# motor_sch.net
KiCad netlist of a schematic drawn in Altium Designer
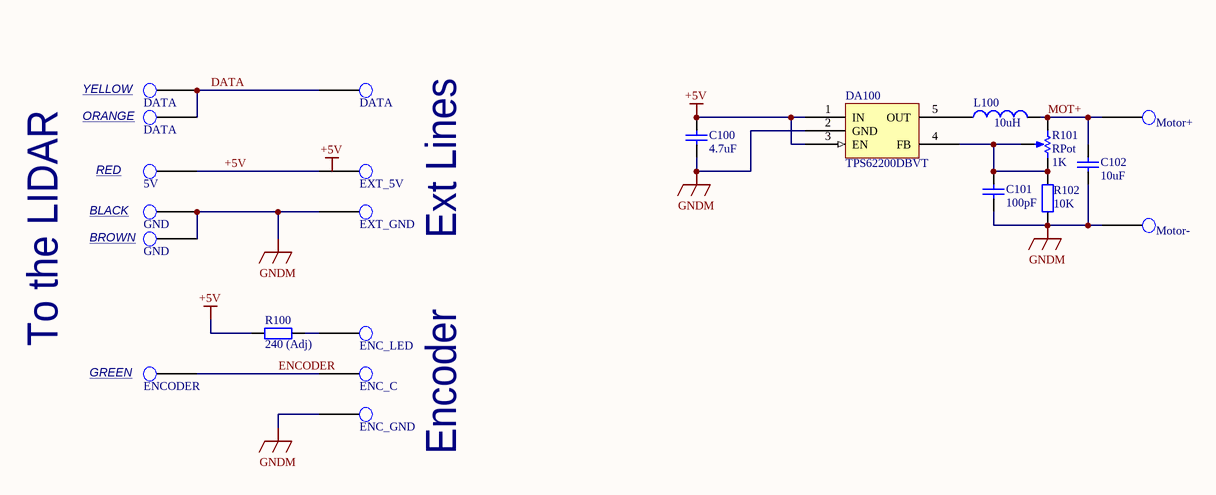
[diagram p0: motor_sch.SchDoc]

(export (version "E")
  (design (tool "Eeschema 10.0.6"))
  (components
    (comp (ref "C100")
      (value "4.7uF")
      (footprint "CAPC2012X135N")
      (description "Chip capacitor")
      (fields (field (name "VOLTAGE") "25V"))
      (libsource (lib "MyLibSch") (part "CC0805"))
    )
    (comp (ref "C101")
      (value "100pF")
      (footprint "CAPC1608X90N")
      (description "Chip capacitor")
      (fields (field (name "VOLTAGE") "25V"))
      (libsource (lib "MyLibSch") (part "CC0805"))
    )
    (comp (ref "C102")
      (value "10uF")
      (footprint "CAPC3216X100N")
      (description "Chip capacitor")
      (fields (field (name "VOLTAGE") "25V"))
      (libsource (lib "MyLibSch") (part "CC0805"))
    )
    (comp (ref "DA100")
      (value "TPS62200DBVT")
      (footprint "SOT23-5")
      (description "DC-DC step-down")
      (libsource (lib "lcd_lib") (part "TPS62200"))
    )
    (comp (ref "L100")
      (value "10uH")
      (footprint "INDC3216")
      (description "Inductor")
      (fields (field (name "PUBLISHER") "Altium Limited"))
      (libsource (lib "Miscellaneous Devices") (part "Inductor"))
    )
    (comp (ref "P101")
      (value "DATA")
      (footprint "Ext_pad")
      (description "Pad for wire")
      (libsource (lib "lcd_lib") (part "Ext Pad"))
    )
    (comp (ref "P102")
      (value "DATA")
      (footprint "Ext_pad")
      (description "Pad for wire")
      (libsource (lib "lcd_lib") (part "Ext Pad"))
    )
    (comp (ref "P103")
      (value "DATA")
      (footprint "Ext_pad")
      (description "Pad for wire")
      (libsource (lib "lcd_lib") (part "Ext Pad"))
    )
    (comp (ref "P104")
      (value "ENC_LED")
      (footprint "Ext_pad")
      (description "Pad for wire")
      (libsource (lib "lcd_lib") (part "Ext Pad"))
    )
    (comp (ref "P105")
      (value "ENC_C")
      (footprint "Ext_pad")
      (description "Pad for wire")
      (libsource (lib "lcd_lib") (part "Ext Pad"))
    )
    (comp (ref "P106")
      (value "ENC_GND")
      (footprint "Ext_pad")
      (description "Pad for wire")
      (libsource (lib "lcd_lib") (part "Ext Pad"))
    )
    (comp (ref "P107")
      (value "ENCODER")
      (footprint "Ext_pad")
      (description "Pad for wire")
      (libsource (lib "lcd_lib") (part "Ext Pad"))
    )
    (comp (ref "P109")
      (value "5V")
      (footprint "Ext_pad")
      (description "Pad for wire")
      (libsource (lib "lcd_lib") (part "Ext Pad"))
    )
    (comp (ref "P110")
      (value "EXT_5V")
      (footprint "Ext_pad")
      (description "Pad for wire")
      (libsource (lib "lcd_lib") (part "Ext Pad"))
    )
    (comp (ref "P111")
      (value "EXT_GND")
      (footprint "Ext_pad")
      (description "Pad for wire")
      (libsource (lib "lcd_lib") (part "Ext Pad"))
    )
    (comp (ref "P112")
      (value "Motor+")
      (footprint "PcbLib3:Ext_hole")
      (description "Hole Pad")
      (libsource (lib "lcd_lib") (part "Hole Pad"))
    )
    (comp (ref "P113")
      (value "Motor-")
      (footprint "PcbLib3:Ext_hole")
      (description "Hole Pad")
      (libsource (lib "lcd_lib") (part "Hole Pad"))
    )
    (comp (ref "P114")
      (value "GND")
      (footprint "Ext_pad")
      (description "Pad for wire")
      (libsource (lib "lcd_lib") (part "Ext Pad"))
    )
    (comp (ref "P115")
      (value "GND")
      (footprint "Ext_pad")
      (description "Pad for wire")
      (libsource (lib "lcd_lib") (part "Ext Pad"))
    )
    (comp (ref "R100")
      (value "240 (Adj)")
      (footprint "RESC1608X55N")
      (description "Chip resistor")
      (fields (field (name "TOLERANCE") "5%"))
      (libsource (lib "MyLibSch") (part "RC0805"))
    )
    (comp (ref "R101")
      (value "RPot")
      (footprint "VR5")
      (description "Potentiometer")
      (fields (field (name "ALTIUM_VALUE") "1K") (field (name "PUBLISHER") "Altium Limited"))
      (libsource (lib "Miscellaneous Devices") (part "RPot"))
    )
    (comp (ref "R102")
      (value "10K")
      (footprint "RESC1608X55N")
      (description "Chip resistor")
      (fields (field (name "TOLERANCE") "5%"))
      (libsource (lib "") (part "RC0805_1"))
    )
  )
  (nets
    (net (code "1") (name "+5V") (class "Default")
      (node (ref "C100") (pin "2") (pinfunction "2_2") (pintype "passive"))
      (node (ref "DA100") (pin "1") (pinfunction "IN_1") (pintype "power_in"))
      (node (ref "DA100") (pin "3") (pinfunction "EN_3") (pintype "input"))
      (node (ref "P109") (pin "1") (pinfunction "Pad_1") (pintype "passive"))
      (node (ref "P110") (pin "1") (pinfunction "Pad_1") (pintype "passive"))
      (node (ref "R100") (pin "2") (pinfunction "2_2") (pintype "passive"))
    )
    (net (code "2") (name "/DATA") (class "Default")
      (node (ref "P101") (pin "1") (pinfunction "Pad_1") (pintype "passive"))
      (node (ref "P102") (pin "1") (pinfunction "Pad_1") (pintype "passive"))
      (node (ref "P103") (pin "1") (pinfunction "Pad_1") (pintype "passive"))
    )
    (net (code "3") (name "/ENCODER") (class "Default")
      (node (ref "P105") (pin "1") (pinfunction "Pad_1") (pintype "passive"))
      (node (ref "P107") (pin "1") (pinfunction "Pad_1") (pintype "passive"))
    )
    (net (code "4") (name "/MOT+") (class "Default")
      (node (ref "C102") (pin "2") (pinfunction "2_2") (pintype "passive"))
      (node (ref "L100") (pin "2") (pinfunction "2_2") (pintype "passive"))
      (node (ref "P112") (pin "1") (pinfunction "Pad_1") (pintype "passive"))
      (node (ref "R101") (pin "1") (pinfunction "TOP_1") (pintype "passive"))
    )
    (net (code "5") (name "GNDM") (class "Default")
      (node (ref "C100") (pin "1") (pinfunction "1_1") (pintype "passive"))
      (node (ref "C101") (pin "1") (pinfunction "1_1") (pintype "passive"))
      (node (ref "C102") (pin "1") (pinfunction "1_1") (pintype "passive"))
      (node (ref "DA100") (pin "2") (pinfunction "GND_2") (pintype "power_in"))
      (node (ref "P106") (pin "1") (pinfunction "Pad_1") (pintype "passive"))
      (node (ref "P111") (pin "1") (pinfunction "Pad_1") (pintype "passive"))
      (node (ref "P113") (pin "1") (pinfunction "Pad_1") (pintype "passive"))
      (node (ref "P114") (pin "1") (pinfunction "Pad_1") (pintype "passive"))
      (node (ref "P115") (pin "1") (pinfunction "Pad_1") (pintype "passive"))
      (node (ref "R102") (pin "1") (pinfunction "1_1") (pintype "passive"))
    )
    (net (code "6") (name "Net-(DA100-FB)") (class "Default")
      (node (ref "C101") (pin "2") (pinfunction "2_2") (pintype "passive"))
      (node (ref "DA100") (pin "4") (pinfunction "FB_4") (pintype "passive"))
      (node (ref "R101") (pin "2") (pinfunction "BOT_2") (pintype "passive"))
      (node (ref "R101") (pin "3") (pinfunction "TAP_3") (pintype "passive"))
      (node (ref "R102") (pin "2") (pinfunction "2_2") (pintype "passive"))
    )
    (net (code "7") (name "Net-(DA100-OUT)") (class "Default")
      (node (ref "DA100") (pin "5") (pinfunction "OUT_5") (pintype "passive"))
      (node (ref "L100") (pin "1") (pinfunction "1_1") (pintype "passive"))
    )
    (net (code "8") (name "Net-(P104-Pad)") (class "Default")
      (node (ref "P104") (pin "1") (pinfunction "Pad_1") (pintype "passive"))
      (node (ref "R100") (pin "1") (pinfunction "1_1") (pintype "passive"))
    )
  )
)
